# G4_TechWatch-BOTTOM.net
KiCad netlist of a schematic drawn in EAGLE
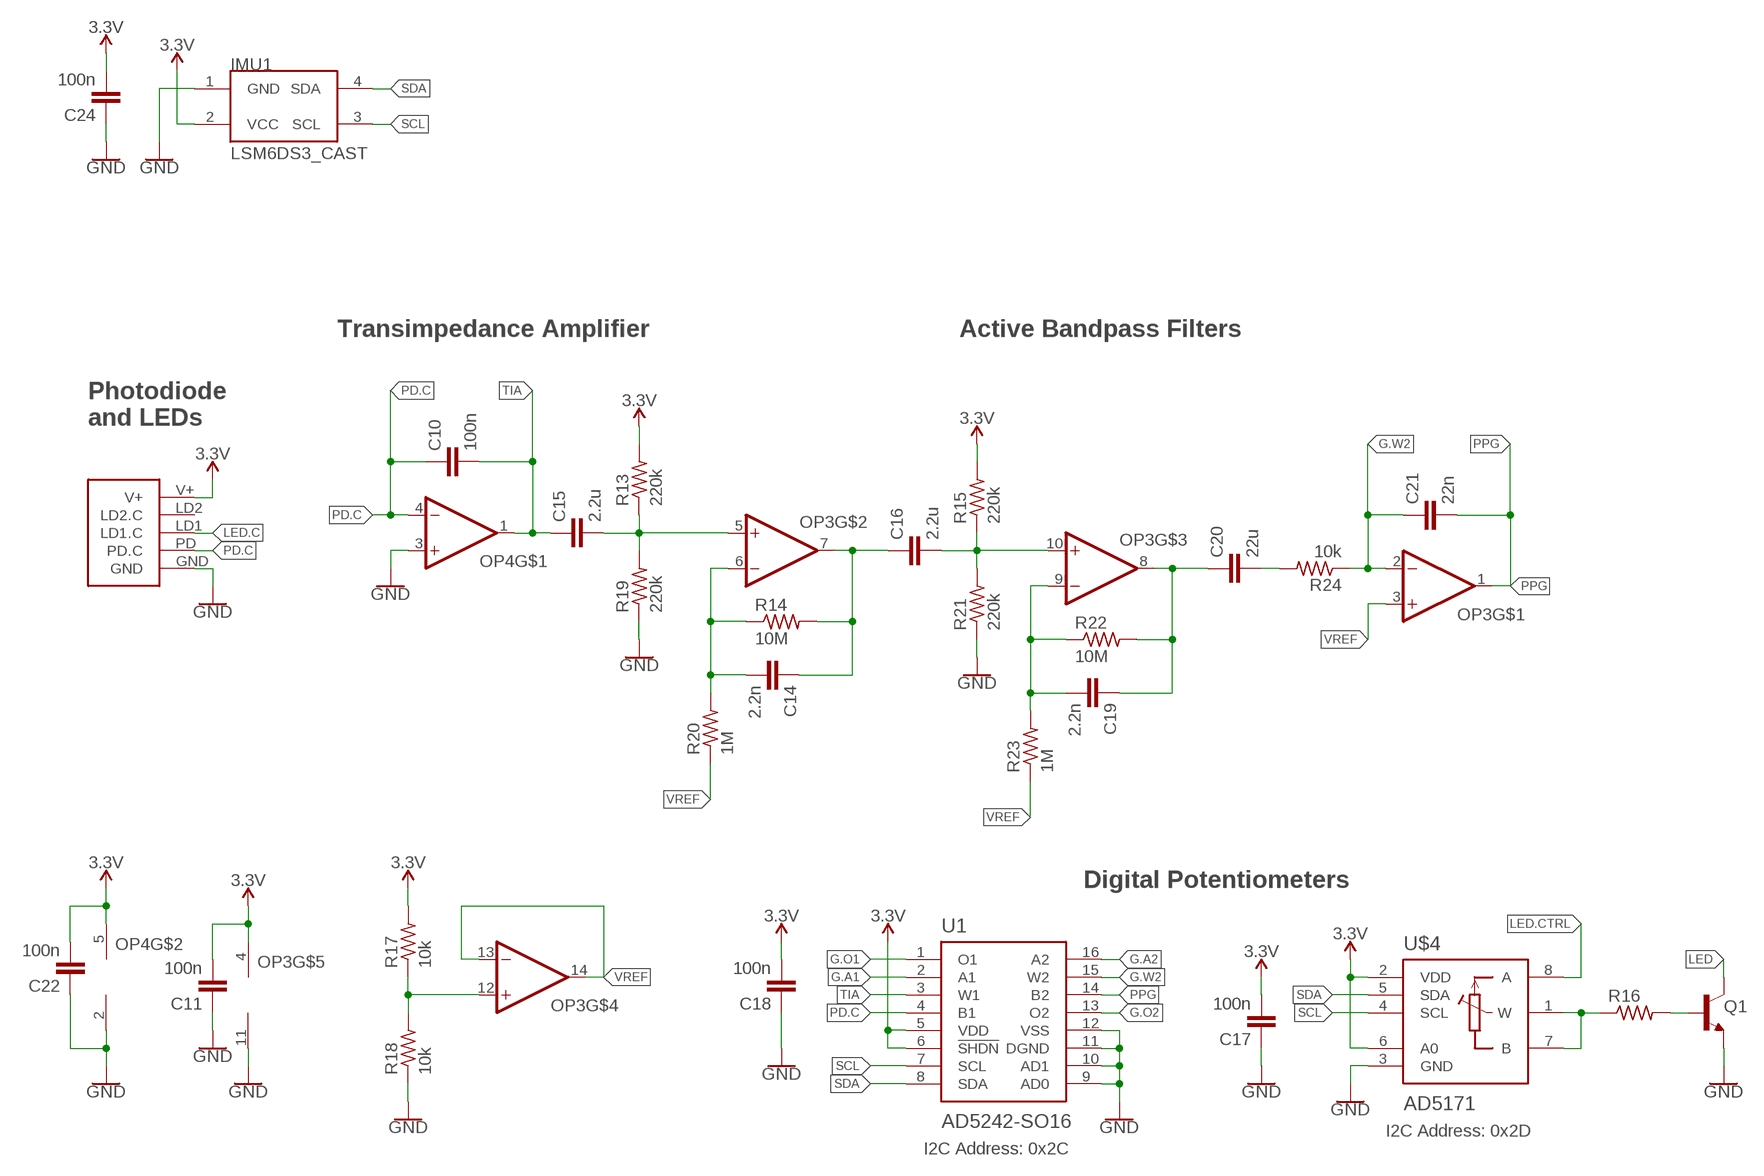
[diagram p0: schematic, sheet 1]

(export (version "E")
  (design (tool "Eeschema 10.0.6"))
  (components
    (comp (ref "C10")
      (value "100n")
      (footprint "eagle-import:C0603")
      (libsource (lib "eagle-import") (part "CAPACITOR0603"))
    )
    (comp (ref "C11")
      (value "100n")
      (footprint "eagle-import:C0603")
      (libsource (lib "eagle-import") (part "CAPACITOR0603"))
    )
    (comp (ref "C14")
      (value "2.2n")
      (footprint "eagle-import:C0603")
      (libsource (lib "eagle-import") (part "CAPACITOR0603"))
    )
    (comp (ref "C15")
      (value "2.2u")
      (footprint "eagle-import:C0603")
      (libsource (lib "eagle-import") (part "CAPACITOR0603"))
    )
    (comp (ref "C16")
      (value "2.2u")
      (footprint "eagle-import:C0603")
      (libsource (lib "eagle-import") (part "CAPACITOR0603"))
    )
    (comp (ref "C17")
      (value "100n")
      (footprint "eagle-import:C0603")
      (libsource (lib "eagle-import") (part "CAPACITOR0603"))
    )
    (comp (ref "C18")
      (value "100n")
      (footprint "eagle-import:C0603")
      (libsource (lib "eagle-import") (part "CAPACITOR0603"))
    )
    (comp (ref "C19")
      (value "2.2n")
      (footprint "eagle-import:C0603")
      (libsource (lib "eagle-import") (part "CAPACITOR0603"))
    )
    (comp (ref "C20")
      (value "22u")
      (footprint "eagle-import:C0603")
      (libsource (lib "eagle-import") (part "CAPACITOR0603"))
    )
    (comp (ref "C21")
      (value "22n")
      (footprint "eagle-import:C0603")
      (libsource (lib "eagle-import") (part "CAPACITOR0603"))
    )
    (comp (ref "C22")
      (value "100n")
      (footprint "eagle-import:C0603")
      (libsource (lib "eagle-import") (part "CAPACITOR0603"))
    )
    (comp (ref "C24")
      (value "100n")
      (footprint "eagle-import:C0603")
      (libsource (lib "eagle-import") (part "CAPACITOR0603"))
    )
    (comp (ref "IMU1")
      (value "LSM6DS3_CAST")
      (footprint "eagle-import:LSM6DS3_CAST")
      (libsource (lib "eagle-import") (part "LSM6DS3_CAST"))
    )
    (comp (ref "OP3")
      (value "OP-QUAD-SO14")
      (footprint "eagle-import:SO14")
      (libsource (lib "eagle-import") (part "OP-QUAD-SO14"))
    )
    (comp (ref "OP4")
      (value "OP-SINGLEOT")
      (footprint "eagle-import:SOT23-5")
      (libsource (lib "eagle-import") (part "OP-SINGLEOT"))
    )
    (comp (ref "Q1")
      (value "NPN-GENERIC")
      (footprint "eagle-import:SOT23-3")
      (libsource (lib "eagle-import") (part "NPN-GENERIC"))
    )
    (comp (ref "R13")
      (value "220k")
      (footprint "eagle-import:R0603")
      (libsource (lib "eagle-import") (part "RESISTOR0603"))
    )
    (comp (ref "R14")
      (value "10M")
      (footprint "eagle-import:R0603")
      (libsource (lib "eagle-import") (part "RESISTOR0603"))
    )
    (comp (ref "R15")
      (value "220k")
      (footprint "eagle-import:R0603")
      (libsource (lib "eagle-import") (part "RESISTOR0603"))
    )
    (comp (ref "R16")
      (value "RESISTOR0603")
      (footprint "eagle-import:R0603")
      (libsource (lib "eagle-import") (part "RESISTOR0603"))
    )
    (comp (ref "R17")
      (value "10k")
      (footprint "eagle-import:R0402")
      (libsource (lib "eagle-import") (part "RESISTOR0402"))
    )
    (comp (ref "R18")
      (value "10k")
      (footprint "eagle-import:R0402")
      (libsource (lib "eagle-import") (part "RESISTOR0402"))
    )
    (comp (ref "R19")
      (value "220k")
      (footprint "eagle-import:R0603")
      (libsource (lib "eagle-import") (part "RESISTOR0603"))
    )
    (comp (ref "R20")
      (value "1M")
      (footprint "eagle-import:R0603")
      (libsource (lib "eagle-import") (part "RESISTOR0603"))
    )
    (comp (ref "R21")
      (value "220k")
      (footprint "eagle-import:R0603")
      (libsource (lib "eagle-import") (part "RESISTOR0603"))
    )
    (comp (ref "R22")
      (value "10M")
      (footprint "eagle-import:R0603")
      (libsource (lib "eagle-import") (part "RESISTOR0603"))
    )
    (comp (ref "R23")
      (value "1M")
      (footprint "eagle-import:R0603")
      (libsource (lib "eagle-import") (part "RESISTOR0603"))
    )
    (comp (ref "R24")
      (value "10k")
      (footprint "eagle-import:R0603")
      (libsource (lib "eagle-import") (part "RESISTOR0603"))
    )
    (comp (ref "U$3")
      (value "PPG.MODULE.2")
      (footprint "eagle-import:PPG.MODULE.2")
      (libsource (lib "eagle-import") (part "PPG.MODULE.2"))
    )
    (comp (ref "U$4")
      (value "AD5171")
      (footprint "eagle-import:SOT-23-8")
      (libsource (lib "eagle-import") (part "AD5171"))
    )
    (comp (ref "U1")
      (value "AD5242-SO16")
      (footprint "eagle-import:SO16")
      (libsource (lib "eagle-import") (part "AD5242-SO16"))
    )
  )
  (nets
    (net (code "1") (name "3.3V") (class "Default")
      (node (ref "C11") (pin "2") (pinfunction "2_2") (pintype "passive"))
      (node (ref "C17") (pin "2") (pinfunction "2_2") (pintype "passive"))
      (node (ref "C18") (pin "2") (pinfunction "2_2") (pintype "passive"))
      (node (ref "C22") (pin "2") (pinfunction "2_2") (pintype "passive"))
      (node (ref "C24") (pin "2") (pinfunction "2_2") (pintype "passive"))
      (node (ref "IMU1") (pin "2") (pinfunction "VCC_2") (pintype "bidirectional"))
      (node (ref "OP3") (pin "4") (pinfunction "V+_4") (pintype "power_in"))
      (node (ref "OP4") (pin "5") (pinfunction "V+_5") (pintype "power_in"))
      (node (ref "R13") (pin "2") (pinfunction "2_2") (pintype "passive"))
      (node (ref "R15") (pin "2") (pinfunction "2_2") (pintype "passive"))
      (node (ref "R17") (pin "2") (pinfunction "2_2") (pintype "passive"))
      (node (ref "U$3") (pin "V+") (pinfunction "V+_V+") (pintype "bidirectional"))
      (node (ref "U$4") (pin "2") (pinfunction "VDD_2") (pintype "bidirectional"))
      (node (ref "U$4") (pin "6") (pinfunction "A0_6") (pintype "bidirectional"))
      (node (ref "U1") (pin "5") (pinfunction "VDD_5") (pintype "bidirectional"))
      (node (ref "U1") (pin "6") (pinfunction "~{SHDN}_6") (pintype "bidirectional"))
    )
    (net (code "2") (name "G.A1") (class "Default")
      (node (ref "U1") (pin "2") (pinfunction "A1_2") (pintype "bidirectional"))
    )
    (net (code "3") (name "G.A2") (class "Default")
      (node (ref "U1") (pin "16") (pinfunction "A2_16") (pintype "bidirectional"))
    )
    (net (code "4") (name "G.O1") (class "Default")
      (node (ref "U1") (pin "1") (pinfunction "O1_1") (pintype "bidirectional"))
    )
    (net (code "5") (name "G.O2") (class "Default")
      (node (ref "U1") (pin "13") (pinfunction "O2_13") (pintype "bidirectional"))
    )
    (net (code "6") (name "G.W2") (class "Default")
      (node (ref "C21") (pin "1") (pinfunction "1_1") (pintype "passive"))
      (node (ref "OP3") (pin "2") (pinfunction "-IN_2") (pintype "input"))
      (node (ref "R24") (pin "1") (pinfunction "1_1") (pintype "passive"))
      (node (ref "U1") (pin "15") (pinfunction "W2_15") (pintype "bidirectional"))
    )
    (net (code "7") (name "GND") (class "Default")
      (node (ref "C11") (pin "1") (pinfunction "1_1") (pintype "passive"))
      (node (ref "C17") (pin "1") (pinfunction "1_1") (pintype "passive"))
      (node (ref "C18") (pin "1") (pinfunction "1_1") (pintype "passive"))
      (node (ref "C22") (pin "1") (pinfunction "1_1") (pintype "passive"))
      (node (ref "C24") (pin "1") (pinfunction "1_1") (pintype "passive"))
      (node (ref "IMU1") (pin "1") (pinfunction "GND_1") (pintype "bidirectional"))
      (node (ref "OP3") (pin "11") (pinfunction "V-_11") (pintype "power_in"))
      (node (ref "OP4") (pin "2") (pinfunction "V-_2") (pintype "power_in"))
      (node (ref "OP4") (pin "3") (pinfunction "+IN_3") (pintype "input"))
      (node (ref "Q1") (pin "2") (pinfunction "E_2") (pintype "passive"))
      (node (ref "R18") (pin "1") (pinfunction "1_1") (pintype "passive"))
      (node (ref "R19") (pin "1") (pinfunction "1_1") (pintype "passive"))
      (node (ref "R21") (pin "1") (pinfunction "1_1") (pintype "passive"))
      (node (ref "U$3") (pin "GND") (pinfunction "GND_GND") (pintype "bidirectional"))
      (node (ref "U$4") (pin "3") (pinfunction "GND_3") (pintype "bidirectional"))
      (node (ref "U1") (pin "10") (pinfunction "AD1_10") (pintype "bidirectional"))
      (node (ref "U1") (pin "11") (pinfunction "DGND_11") (pintype "bidirectional"))
      (node (ref "U1") (pin "12") (pinfunction "VSS_12") (pintype "bidirectional"))
      (node (ref "U1") (pin "9") (pinfunction "AD0_9") (pintype "bidirectional"))
    )
    (net (code "8") (name "LED") (class "Default")
      (node (ref "Q1") (pin "3") (pinfunction "C_3") (pintype "passive"))
    )
    (net (code "9") (name "LED.C") (class "Default")
      (node (ref "U$3") (pin "LD1") (pinfunction "LD1.C_LD1") (pintype "bidirectional"))
    )
    (net (code "10") (name "LED.CTRL") (class "Default")
      (node (ref "U$4") (pin "8") (pinfunction "A_8") (pintype "bidirectional"))
    )
    (net (code "11") (name "Net-(C20-Pad2)") (class "Default")
      (node (ref "C20") (pin "2") (pinfunction "2_2") (pintype "passive"))
      (node (ref "R24") (pin "2") (pinfunction "2_2") (pintype "passive"))
    )
    (net (code "12") (name "Net-(OP3B-+IN)") (class "Default")
      (node (ref "C15") (pin "2") (pinfunction "2_2") (pintype "passive"))
      (node (ref "OP3") (pin "5") (pinfunction "+IN_5") (pintype "input"))
      (node (ref "R13") (pin "1") (pinfunction "1_1") (pintype "passive"))
      (node (ref "R19") (pin "2") (pinfunction "2_2") (pintype "passive"))
    )
    (net (code "13") (name "Net-(OP3B--IN)") (class "Default")
      (node (ref "C14") (pin "2") (pinfunction "2_2") (pintype "passive"))
      (node (ref "OP3") (pin "6") (pinfunction "-IN_6") (pintype "input"))
      (node (ref "R14") (pin "1") (pinfunction "1_1") (pintype "passive"))
      (node (ref "R20") (pin "2") (pinfunction "2_2") (pintype "passive"))
    )
    (net (code "14") (name "Net-(OP3B-OUT)") (class "Default")
      (node (ref "C14") (pin "1") (pinfunction "1_1") (pintype "passive"))
      (node (ref "C16") (pin "1") (pinfunction "1_1") (pintype "passive"))
      (node (ref "OP3") (pin "7") (pinfunction "OUT_7") (pintype "output"))
      (node (ref "R14") (pin "2") (pinfunction "2_2") (pintype "passive"))
    )
    (net (code "15") (name "Net-(OP3C-+IN)") (class "Default")
      (node (ref "C16") (pin "2") (pinfunction "2_2") (pintype "passive"))
      (node (ref "OP3") (pin "10") (pinfunction "+IN_10") (pintype "input"))
      (node (ref "R15") (pin "1") (pinfunction "1_1") (pintype "passive"))
      (node (ref "R21") (pin "2") (pinfunction "2_2") (pintype "passive"))
    )
    (net (code "16") (name "Net-(OP3C--IN)") (class "Default")
      (node (ref "C19") (pin "2") (pinfunction "2_2") (pintype "passive"))
      (node (ref "OP3") (pin "9") (pinfunction "-IN_9") (pintype "input"))
      (node (ref "R22") (pin "1") (pinfunction "1_1") (pintype "passive"))
      (node (ref "R23") (pin "2") (pinfunction "2_2") (pintype "passive"))
    )
    (net (code "17") (name "Net-(OP3C-OUT)") (class "Default")
      (node (ref "C19") (pin "1") (pinfunction "1_1") (pintype "passive"))
      (node (ref "C20") (pin "1") (pinfunction "1_1") (pintype "passive"))
      (node (ref "OP3") (pin "8") (pinfunction "OUT_8") (pintype "output"))
      (node (ref "R22") (pin "2") (pinfunction "2_2") (pintype "passive"))
    )
    (net (code "18") (name "Net-(OP3D-+IN)") (class "Default")
      (node (ref "OP3") (pin "12") (pinfunction "+IN_12") (pintype "input"))
      (node (ref "R17") (pin "1") (pinfunction "1_1") (pintype "passive"))
      (node (ref "R18") (pin "2") (pinfunction "2_2") (pintype "passive"))
    )
    (net (code "19") (name "Net-(Q1-B)") (class "Default")
      (node (ref "Q1") (pin "1") (pinfunction "B_1") (pintype "passive"))
      (node (ref "R16") (pin "2") (pinfunction "2_2") (pintype "passive"))
    )
    (net (code "20") (name "Net-(U$4-B)") (class "Default")
      (node (ref "R16") (pin "1") (pinfunction "1_1") (pintype "passive"))
      (node (ref "U$4") (pin "1") (pinfunction "W_1") (pintype "bidirectional"))
      (node (ref "U$4") (pin "7") (pinfunction "B_7") (pintype "bidirectional"))
    )
    (net (code "21") (name "PD.C") (class "Default")
      (node (ref "C10") (pin "1") (pinfunction "1_1") (pintype "passive"))
      (node (ref "OP4") (pin "4") (pinfunction "-IN_4") (pintype "input"))
      (node (ref "U$3") (pin "PD") (pinfunction "PD.C_PD") (pintype "bidirectional"))
      (node (ref "U1") (pin "4") (pinfunction "B1_4") (pintype "bidirectional"))
    )
    (net (code "22") (name "PPG") (class "Default")
      (node (ref "C21") (pin "2") (pinfunction "2_2") (pintype "passive"))
      (node (ref "OP3") (pin "1") (pinfunction "OUT_1") (pintype "output"))
      (node (ref "U1") (pin "14") (pinfunction "B2_14") (pintype "bidirectional"))
    )
    (net (code "23") (name "SCL") (class "Default")
      (node (ref "IMU1") (pin "3") (pinfunction "SCL_3") (pintype "bidirectional"))
      (node (ref "U$4") (pin "4") (pinfunction "SCL_4") (pintype "bidirectional"))
      (node (ref "U1") (pin "7") (pinfunction "SCL_7") (pintype "bidirectional"))
    )
    (net (code "24") (name "SDA") (class "Default")
      (node (ref "IMU1") (pin "4") (pinfunction "SDA_4") (pintype "bidirectional"))
      (node (ref "U$4") (pin "5") (pinfunction "SDA_5") (pintype "bidirectional"))
      (node (ref "U1") (pin "8") (pinfunction "SDA_8") (pintype "bidirectional"))
    )
    (net (code "25") (name "TIA") (class "Default")
      (node (ref "C10") (pin "2") (pinfunction "2_2") (pintype "passive"))
      (node (ref "C15") (pin "1") (pinfunction "1_1") (pintype "passive"))
      (node (ref "OP4") (pin "1") (pinfunction "OUT_1") (pintype "output"))
      (node (ref "U1") (pin "3") (pinfunction "W1_3") (pintype "bidirectional"))
    )
    (net (code "26") (name "VREF") (class "Default")
      (node (ref "OP3") (pin "13") (pinfunction "-IN_13") (pintype "input"))
      (node (ref "OP3") (pin "14") (pinfunction "OUT_14") (pintype "output"))
      (node (ref "OP3") (pin "3") (pinfunction "+IN_3") (pintype "input"))
      (node (ref "R20") (pin "1") (pinfunction "1_1") (pintype "passive"))
      (node (ref "R23") (pin "1") (pinfunction "1_1") (pintype "passive"))
    )
    (net (code "27") (name "unconnected-(U$3-LD2.C-PadLD2)") (class "Default")
      (node (ref "U$3") (pin "LD2") (pinfunction "LD2.C_LD2") (pintype "bidirectional"))
    )
  )
)
